# Sheet1.net
KiCad netlist of a schematic drawn in Altium Designer
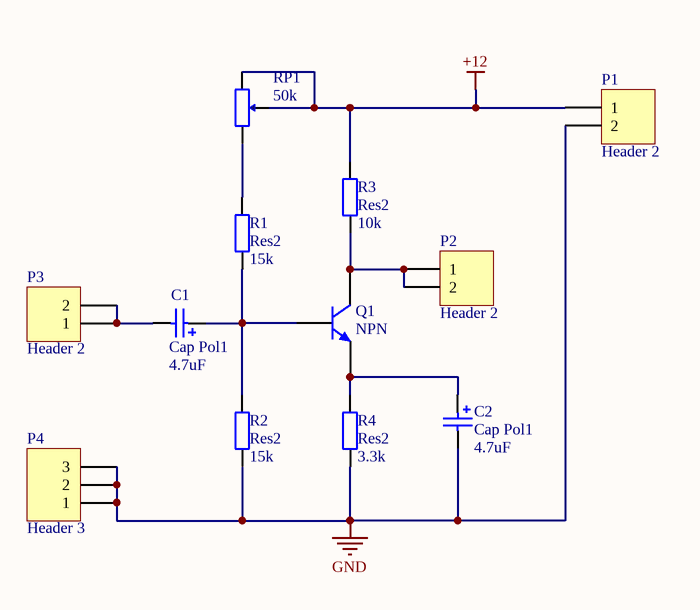
[diagram p0: Sheet1.SchDoc]

(export (version "E")
  (design (tool "Eeschema 10.0.6"))
  (components
    (comp (ref "C1")
      (value "Cap Pol1")
      (footprint "电容:CAP 2.5*6.3*11.2")
      (description "Polarized Capacitor (Axial)")
      (fields (field (name "ALTIUM_VALUE") "4.7uF") (field (name "PUBLISHER") "Altium Limited"))
      (libsource (lib "Miscellaneous Devices") (part "Cap Pol2"))
    )
    (comp (ref "C2")
      (value "Cap Pol1")
      (footprint "CAP 2.5*6.3*11.2")
      (description "Polarized Capacitor (Axial)")
      (fields (field (name "ALTIUM_VALUE") "4.7uF") (field (name "PUBLISHER") "Altium Limited"))
      (libsource (lib "Miscellaneous Devices") (part "Cap Pol2"))
    )
    (comp (ref "P1")
      (value "Header 2")
      (footprint "XH2.54-LI-2P")
      (description "Header, 2-Pin")
      (fields (field (name "PUBLISHER") "Altium Limited"))
      (libsource (lib "") (part "Header 2_1"))
    )
    (comp (ref "P2")
      (value "Header 2")
      (footprint "HDR1X2")
      (description "Header, 2-Pin")
      (fields (field (name "PUBLISHER") "Altium Limited"))
      (libsource (lib "") (part "Header 2_1"))
    )
    (comp (ref "P3")
      (value "Header 2")
      (footprint "HDR1X2")
      (description "Header, 2-Pin")
      (fields (field (name "PUBLISHER") "Altium Limited"))
      (libsource (lib "Miscellaneous Connectors") (part "Header 2"))
    )
    (comp (ref "P4")
      (value "Header 3")
      (footprint "HDR1X3")
      (description "Header, 3-Pin")
      (fields (field (name "PUBLISHER") "Altium Limited"))
      (libsource (lib "Miscellaneous Connectors") (part "Header 3"))
    )
    (comp (ref "Q1")
      (value "NPN")
      (footprint "TO92")
      (description "NPN Bipolar Transistor")
      (fields (field (name "PUBLISHER") "Altium Limited"))
      (libsource (lib "Miscellaneous Devices") (part "NPN"))
    )
    (comp (ref "R1")
      (value "Res2")
      (footprint "AXIAL-0.4")
      (description "Resistor")
      (fields (field (name "ALTIUM_VALUE") "15k") (field (name "PUBLISHER") "Altium Limited"))
      (libsource (lib "Miscellaneous Devices") (part "Res2"))
    )
    (comp (ref "R2")
      (value "Res2")
      (footprint "AXIAL-0.4")
      (description "Resistor")
      (fields (field (name "ALTIUM_VALUE") "15k") (field (name "PUBLISHER") "Altium Limited"))
      (libsource (lib "Miscellaneous Devices") (part "Res2"))
    )
    (comp (ref "R3")
      (value "Res2")
      (footprint "AXIAL-0.4")
      (description "Resistor")
      (fields (field (name "ALTIUM_VALUE") "10k") (field (name "PUBLISHER") "Altium Limited"))
      (libsource (lib "Miscellaneous Devices") (part "Res2"))
    )
    (comp (ref "R4")
      (value "Res2")
      (footprint "AXIAL-0.4")
      (description "Resistor")
      (fields (field (name "ALTIUM_VALUE") "3.3k") (field (name "PUBLISHER") "Altium Limited"))
      (libsource (lib "Miscellaneous Devices") (part "Res2"))
    )
    (comp (ref "RP1")
      (value "50k")
      (footprint "3296W")
      (description "插件单联电位器")
      (fields (field (name "版权归属") "源创客"))
      (libsource (lib "3.1   - 电阻-电容-电感") (part "RP-ID"))
    )
  )
  (nets
    (net (code "1") (name "+12") (class "Default")
      (node (ref "P1") (pin "1") (pinfunction "1_1") (pintype "passive"))
      (node (ref "R3") (pin "2") (pinfunction "2_2") (pintype "passive"))
      (node (ref "RP1") (pin "1") (pinfunction "1_1") (pintype "passive"))
      (node (ref "RP1") (pin "2") (pinfunction "2_2") (pintype "passive"))
    )
    (net (code "2") (name "GND") (class "Default")
      (node (ref "C2") (pin "2") (pinfunction "2_2") (pintype "passive"))
      (node (ref "P1") (pin "2") (pinfunction "2_2") (pintype "passive"))
      (node (ref "P4") (pin "1") (pinfunction "1_1") (pintype "passive"))
      (node (ref "P4") (pin "2") (pinfunction "2_2") (pintype "passive"))
      (node (ref "P4") (pin "3") (pinfunction "3_3") (pintype "passive"))
      (node (ref "R2") (pin "1") (pinfunction "1_1") (pintype "passive"))
      (node (ref "R4") (pin "1") (pinfunction "1_1") (pintype "passive"))
    )
    (net (code "3") (name "Net-(C1-Pad2)") (class "Default")
      (node (ref "C1") (pin "2") (pinfunction "2_2") (pintype "passive"))
      (node (ref "P3") (pin "1") (pinfunction "1_1") (pintype "passive"))
      (node (ref "P3") (pin "2") (pinfunction "2_2") (pintype "passive"))
    )
    (net (code "4") (name "Net-(Q1-B)") (class "Default")
      (node (ref "C1") (pin "1") (pinfunction "1_1") (pintype "passive"))
      (node (ref "Q1") (pin "2") (pinfunction "B_2") (pintype "passive"))
      (node (ref "R1") (pin "1") (pinfunction "1_1") (pintype "passive"))
      (node (ref "R2") (pin "2") (pinfunction "2_2") (pintype "passive"))
    )
    (net (code "5") (name "Net-(Q1-C)") (class "Default")
      (node (ref "P2") (pin "1") (pinfunction "1_1") (pintype "passive"))
      (node (ref "P2") (pin "2") (pinfunction "2_2") (pintype "passive"))
      (node (ref "Q1") (pin "1") (pinfunction "C_1") (pintype "passive"))
      (node (ref "R3") (pin "1") (pinfunction "1_1") (pintype "passive"))
    )
    (net (code "6") (name "Net-(Q1-E)") (class "Default")
      (node (ref "C2") (pin "1") (pinfunction "1_1") (pintype "passive"))
      (node (ref "Q1") (pin "3") (pinfunction "E_3") (pintype "passive"))
      (node (ref "R4") (pin "2") (pinfunction "2_2") (pintype "passive"))
    )
    (net (code "7") (name "Net-(R1-Pad2)") (class "Default")
      (node (ref "R1") (pin "2") (pinfunction "2_2") (pintype "passive"))
      (node (ref "RP1") (pin "3") (pinfunction "3_3") (pintype "passive"))
    )
  )
)
